# Card_Edge_Connector.net
KiCad netlist of a schematic drawn in Altium Designer
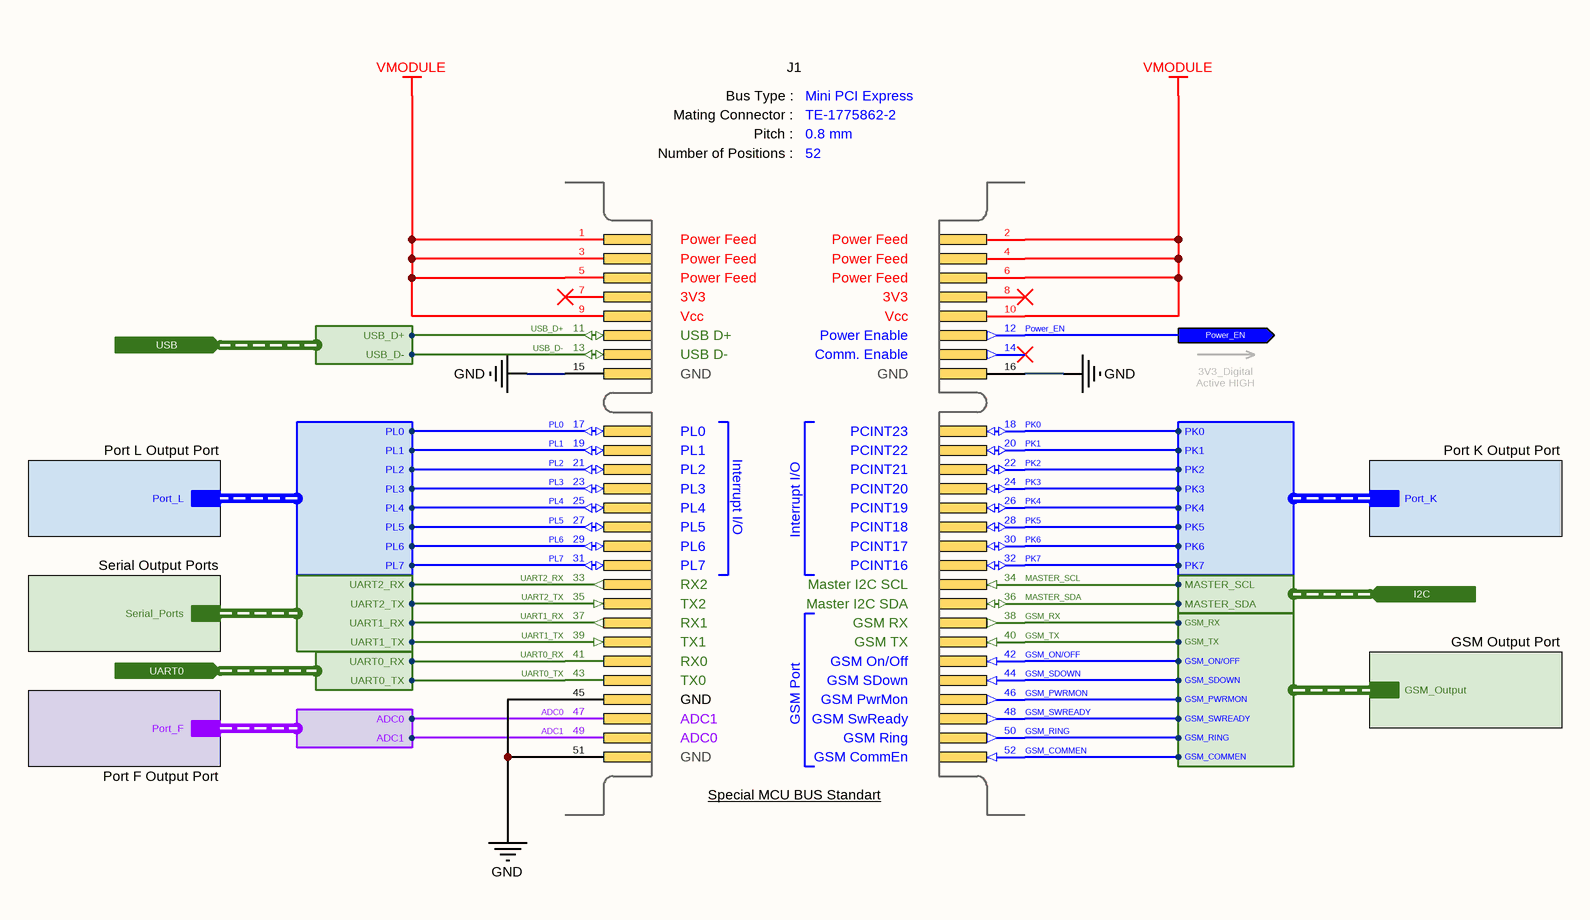
[diagram p0: Card Edge Connector.SchDoc]

(export (version "E")
  (design (tool "Eeschema 10.0.6"))
  (components
    (comp (ref "J1")
      (value "PCI-E Connector")
      (footprint "PCB - Mini PCI Express")
      (description "Mini PCI-Express gold finger connector.")
      (fields
        (field (name "BUS TYPE") "Mini PCI Express")
        (field (name "MATING CONNECTOR") "TE-1775862-2")
        (field (name "PITCH") "0.8 mm")
        (field (name "NUMBER OF POSITIONS") "52")
      )
      (libsource (lib "P101DA_Library") (part "Connector - Mini PCI-E [MCU]"))
    )
  )
  (nets
    (net (code "9") (name "/ADC0") (class "Default")
      (node (ref "J1") (pin "47") (pinfunction "Pin-47_47") (pintype "passive"))
    )
    (net (code "10") (name "/ADC1") (class "Default")
      (node (ref "J1") (pin "49") (pinfunction "Pin-49_49") (pintype "passive"))
    )
    (net (code "11") (name "/GSM_COMMEN") (class "Default")
      (node (ref "J1") (pin "52") (pinfunction "Pin-52_52") (pintype "input"))
    )
    (net (code "12") (name "/GSM_ON{slash}OFF") (class "Default")
      (node (ref "J1") (pin "42") (pinfunction "Pin-42_42") (pintype "input"))
    )
    (net (code "13") (name "/GSM_PWRMON") (class "Default")
      (node (ref "J1") (pin "46") (pinfunction "Pin-46_46") (pintype "output"))
    )
    (net (code "14") (name "/GSM_RING") (class "Default")
      (node (ref "J1") (pin "50") (pinfunction "Pin-50_50") (pintype "output"))
    )
    (net (code "15") (name "/GSM_RX") (class "Default")
      (node (ref "J1") (pin "38") (pinfunction "Pin-38_38") (pintype "output"))
    )
    (net (code "16") (name "/GSM_SDOWN") (class "Default")
      (node (ref "J1") (pin "44") (pinfunction "Pin-44_44") (pintype "input"))
    )
    (net (code "17") (name "/GSM_SWREADY") (class "Default")
      (node (ref "J1") (pin "48") (pinfunction "Pin-48_48") (pintype "output"))
    )
    (net (code "18") (name "/GSM_TX") (class "Default")
      (node (ref "J1") (pin "40") (pinfunction "Pin-40_40") (pintype "input"))
    )
    (net (code "19") (name "/MASTER_SCL") (class "Default")
      (node (ref "J1") (pin "34") (pinfunction "Pin-34_34") (pintype "input"))
    )
    (net (code "20") (name "/MASTER_SDA") (class "Default")
      (node (ref "J1") (pin "36") (pinfunction "Pin-36_36") (pintype "bidirectional"))
    )
    (net (code "21") (name "/PK0") (class "Default")
      (node (ref "J1") (pin "18") (pinfunction "Pin-18_18") (pintype "bidirectional"))
    )
    (net (code "22") (name "/PK1") (class "Default")
      (node (ref "J1") (pin "20") (pinfunction "Pin-20_20") (pintype "bidirectional"))
    )
    (net (code "23") (name "/PK2") (class "Default")
      (node (ref "J1") (pin "22") (pinfunction "Pin-22_22") (pintype "bidirectional"))
    )
    (net (code "24") (name "/PK3") (class "Default")
      (node (ref "J1") (pin "24") (pinfunction "Pin-24_24") (pintype "bidirectional"))
    )
    (net (code "25") (name "/PK4") (class "Default")
      (node (ref "J1") (pin "26") (pinfunction "Pin-26_26") (pintype "bidirectional"))
    )
    (net (code "26") (name "/PK5") (class "Default")
      (node (ref "J1") (pin "28") (pinfunction "Pin-28_28") (pintype "bidirectional"))
    )
    (net (code "27") (name "/PK6") (class "Default")
      (node (ref "J1") (pin "30") (pinfunction "Pin-30_30") (pintype "bidirectional"))
    )
    (net (code "28") (name "/PK7") (class "Default")
      (node (ref "J1") (pin "32") (pinfunction "Pin-32_32") (pintype "bidirectional"))
    )
    (net (code "29") (name "/PL0") (class "Default")
      (node (ref "J1") (pin "17") (pinfunction "Pin-17_17") (pintype "bidirectional"))
    )
    (net (code "30") (name "/PL1") (class "Default")
      (node (ref "J1") (pin "19") (pinfunction "Pin-19_19") (pintype "bidirectional"))
    )
    (net (code "31") (name "/PL2") (class "Default")
      (node (ref "J1") (pin "21") (pinfunction "Pin-21_21") (pintype "bidirectional"))
    )
    (net (code "32") (name "/PL3") (class "Default")
      (node (ref "J1") (pin "23") (pinfunction "Pin-23_23") (pintype "bidirectional"))
    )
    (net (code "33") (name "/PL4") (class "Default")
      (node (ref "J1") (pin "25") (pinfunction "Pin-25_25") (pintype "bidirectional"))
    )
    (net (code "34") (name "/PL5") (class "Default")
      (node (ref "J1") (pin "27") (pinfunction "Pin-27_27") (pintype "bidirectional"))
    )
    (net (code "35") (name "/PL6") (class "Default")
      (node (ref "J1") (pin "29") (pinfunction "Pin-29_29") (pintype "bidirectional"))
    )
    (net (code "36") (name "/PL7") (class "Default")
      (node (ref "J1") (pin "31") (pinfunction "Pin-31_31") (pintype "bidirectional"))
    )
    (net (code "37") (name "/Power_EN") (class "Default")
      (node (ref "J1") (pin "12") (pinfunction "Pin-12_12") (pintype "output"))
    )
    (net (code "38") (name "/UART0_RX") (class "Default")
      (node (ref "J1") (pin "41") (pinfunction "Pin-41_41") (pintype "passive"))
    )
    (net (code "39") (name "/UART0_TX") (class "Default")
      (node (ref "J1") (pin "43") (pinfunction "Pin-43_43") (pintype "passive"))
    )
    (net (code "40") (name "/UART1_RX") (class "Default")
      (node (ref "J1") (pin "37") (pinfunction "Pin-37_37") (pintype "output"))
    )
    (net (code "41") (name "/UART1_TX") (class "Default")
      (node (ref "J1") (pin "39") (pinfunction "Pin-39_39") (pintype "input"))
    )
    (net (code "42") (name "/UART2_RX") (class "Default")
      (node (ref "J1") (pin "33") (pinfunction "Pin-33_33") (pintype "output"))
    )
    (net (code "43") (name "/UART2_TX") (class "Default")
      (node (ref "J1") (pin "35") (pinfunction "Pin-35_35") (pintype "input"))
    )
    (net (code "44") (name "/USB_D+") (class "Default")
      (node (ref "J1") (pin "11") (pinfunction "Pin-11_11") (pintype "bidirectional"))
    )
    (net (code "45") (name "/USB_D-") (class "Default")
      (node (ref "J1") (pin "13") (pinfunction "Pin-13_13") (pintype "bidirectional"))
    )
    (net (code "54") (name "GND") (class "Default")
      (node (ref "J1") (pin "15") (pinfunction "Pin-15_15") (pintype "power_in"))
      (node (ref "J1") (pin "16") (pinfunction "Pin-16_16") (pintype "power_in"))
      (node (ref "J1") (pin "45") (pinfunction "Pin-45_45") (pintype "passive"))
      (node (ref "J1") (pin "51") (pinfunction "Pin-51_51") (pintype "power_in"))
    )
    (net (code "55") (name "VMODULE") (class "Default")
      (node (ref "J1") (pin "1") (pinfunction "Pin-1_1") (pintype "power_in"))
      (node (ref "J1") (pin "10") (pinfunction "Pin-10_10") (pintype "power_in"))
      (node (ref "J1") (pin "2") (pinfunction "Pin-2_2") (pintype "power_in"))
      (node (ref "J1") (pin "3") (pinfunction "Pin-3_3") (pintype "power_in"))
      (node (ref "J1") (pin "4") (pinfunction "Pin-4_4") (pintype "power_in"))
      (node (ref "J1") (pin "5") (pinfunction "Pin-5_5") (pintype "power_in"))
      (node (ref "J1") (pin "6") (pinfunction "Pin-6_6") (pintype "power_in"))
      (node (ref "J1") (pin "9") (pinfunction "Pin-9_9") (pintype "power_in"))
    )
    (net (code "56") (name "unconnected-(J1-Pin-7-Pad7)") (class "Default")
      (node (ref "J1") (pin "7") (pinfunction "Pin-7_7") (pintype "power_in+no_connect"))
    )
    (net (code "57") (name "unconnected-(J1-Pin-8-Pad8)") (class "Default")
      (node (ref "J1") (pin "8") (pinfunction "Pin-8_8") (pintype "power_in+no_connect"))
    )
    (net (code "58") (name "unconnected-(J1-Pin-14-Pad14)") (class "Default")
      (node (ref "J1") (pin "14") (pinfunction "Pin-14_14") (pintype "output+no_connect"))
    )
  )
)
